# fab.net
KiCad netlist of a schematic drawn in Altium Designer
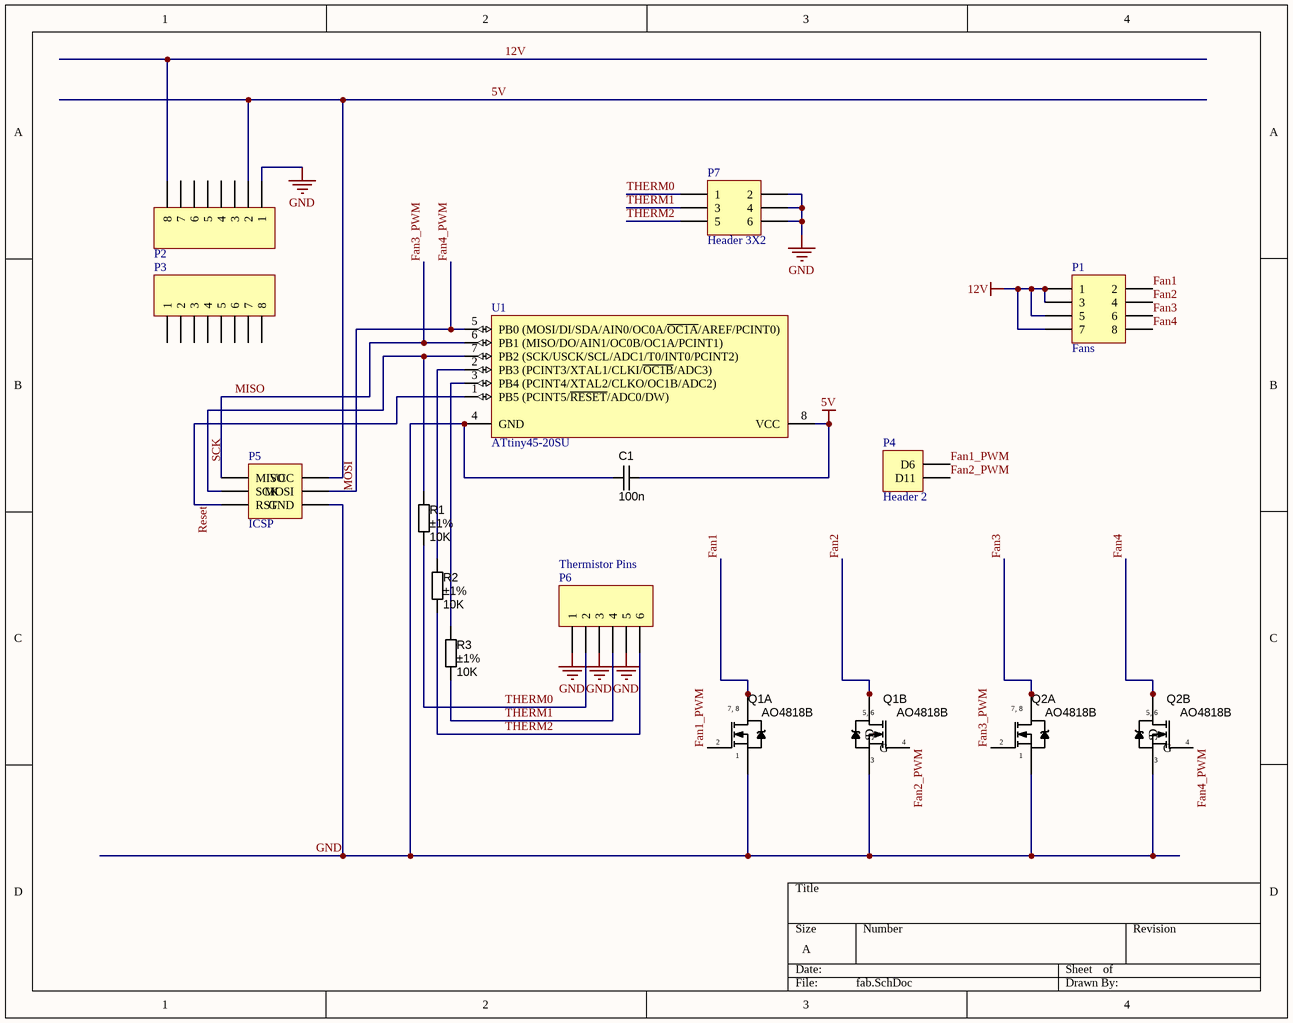
[diagram p0: fab.SchDoc]

(export (version "E")
  (design (tool "Eeschema 10.0.6"))
  (components
    (comp (ref "C1")
      (value "100n")
      (footprint "CAPC1005X55N")
      (description "Capacitor SMD Cer 100nF 10% 16V X5R 0402")
      (fields (field (name "TOLERANCE") "±10%"))
      (libsource (lib "PBL - Capacitors") (part "CAPC_100n_0402_X5R_16V_10%"))
    )
    (comp (ref "P1")
      (value "Fans")
      (footprint "HDR2X4")
      (description "Header, 4-Pin, Dual row")
      (fields (field (name "PUBLISHER") "Altium Limited"))
      (libsource (lib "Miscellaneous Connectors") (part "Header 4X2"))
    )
    (comp (ref "P2")
      (value "Header 8")
      (footprint "HDR1X8")
      (description "Header, 8-Pin")
      (fields (field (name "PUBLISHER") "Altium Limited"))
      (libsource (lib "Miscellaneous Connectors") (part "Header 8"))
    )
    (comp (ref "P3")
      (value "Header 8")
      (footprint "HDR1X8")
      (description "Header, 8-Pin")
      (fields (field (name "PUBLISHER") "Altium Limited"))
      (libsource (lib "") (part "Header 8_1"))
    )
    (comp (ref "P4")
      (value "Header 2")
      (footprint "HDR1X2")
      (description "Header, 2-Pin")
      (fields (field (name "PUBLISHER") "Altium Limited"))
      (libsource (lib "Miscellaneous Connectors") (part "Header 2"))
    )
    (comp (ref "P5")
      (value "ICSP")
      (footprint "ICSP Pads - SMD")
      (description "Header, 3-Pin, Dual row")
      (fields (field (name "PUBLISHER") "Altium Limited"))
      (libsource (lib "") (part "Header 3X2_1"))
    )
    (comp (ref "P6")
      (value "Thermistor Pins")
      (footprint "HDR1X6")
      (description "Header, 6-Pin")
      (fields (field (name "PUBLISHER") "Altium Limited"))
      (libsource (lib "Miscellaneous Connectors") (part "Header 6"))
    )
    (comp (ref "P7")
      (value "Header 3X2")
      (footprint "HDR2X3")
      (description "Header, 3-Pin, Dual row")
      (fields (field (name "PUBLISHER") "Altium Limited"))
      (libsource (lib "Miscellaneous Connectors") (part "Header 3X2"))
    )
    (comp (ref "Q1")
      (value "MOSFET_AO4818B")
      (footprint "SOIC127P600X175-8AN")
      (description "MOSFET Dual-Channel 30V 8.5A SOIC-8 SMD")
      (fields (field (name "MANUFACTURER PART NUMBER 1") "AO4818B"))
      (libsource (lib "PBL - Transistors") (part "MOSFET_AO4818B"))
    )
    (comp (ref "Q2")
      (value "MOSFET_AO4818B")
      (footprint "SOIC127P600X175-8AN")
      (description "MOSFET Dual-Channel 30V 8.5A SOIC-8 SMD")
      (fields (field (name "MANUFACTURER PART NUMBER 1") "AO4818B"))
      (libsource (lib "") (part "MOSFET_AO4818B_1"))
    )
    (comp (ref "R1")
      (value "10K")
      (footprint "RESC1608X55N")
      (description "Resistor SMD chip 10k Ohm 0.1W 1% 0603")
      (fields (field (name "TOLERANCE") "±1%") (field (name "Comment") "Thick Film"))
      (libsource (lib "PBL - Resistors") (part "RES_10K_0603_1%"))
    )
    (comp (ref "R2")
      (value "10K")
      (footprint "RESC1608X55N")
      (description "Resistor SMD chip 10k Ohm 0.1W 1% 0603")
      (fields (field (name "TOLERANCE") "±1%") (field (name "Comment") "Thick Film"))
      (libsource (lib "PBL - Resistors") (part "RES_10K_0603_1%"))
    )
    (comp (ref "R3")
      (value "10K")
      (footprint "RESC1608X55N")
      (description "Resistor SMD chip 10k Ohm 0.1W 1% 0603")
      (fields (field (name "TOLERANCE") "±1%") (field (name "Comment") "Thick Film"))
      (libsource (lib "PBL - Resistors") (part "RES_10K_0603_1%"))
    )
    (comp (ref "U1")
      (value "ATtiny45-20SU")
      (footprint "8S2_N")
      (libsource (lib "Atmel Microcontroller tinyAVR") (part "ATtiny45-20SU"))
    )
  )
  (nets
    (net (code "1") (name "/Fan1") (class "Default")
      (node (ref "P1") (pin "2") (pinfunction "2_2") (pintype "passive"))
      (node (ref "Q1") (pin "7") (pinfunction "D_7") (pintype "passive"))
      (node (ref "Q1") (pin "8") (pinfunction "D_8") (pintype "passive"))
    )
    (net (code "2") (name "/Fan1_PWM") (class "Default")
      (node (ref "P4") (pin "2") (pinfunction "D6_2") (pintype "passive"))
      (node (ref "Q1") (pin "2") (pinfunction "G_2") (pintype "passive"))
    )
    (net (code "3") (name "/Fan2") (class "Default")
      (node (ref "P1") (pin "4") (pinfunction "4_4") (pintype "passive"))
      (node (ref "Q1") (pin "5") (pinfunction "D_5") (pintype "passive"))
      (node (ref "Q1") (pin "6") (pinfunction "D_6") (pintype "passive"))
    )
    (net (code "4") (name "/Fan2_PWM") (class "Default")
      (node (ref "P4") (pin "1") (pinfunction "D11_1") (pintype "passive"))
      (node (ref "Q1") (pin "4") (pinfunction "G_4") (pintype "passive"))
    )
    (net (code "5") (name "/Fan3") (class "Default")
      (node (ref "P1") (pin "6") (pinfunction "6_6") (pintype "passive"))
      (node (ref "Q2") (pin "7") (pinfunction "D_7") (pintype "passive"))
      (node (ref "Q2") (pin "8") (pinfunction "D_8") (pintype "passive"))
    )
    (net (code "6") (name "/Fan3_PWM") (class "Default")
      (node (ref "P5") (pin "0") (pinfunction "MISO_0") (pintype "passive"))
      (node (ref "Q2") (pin "2") (pinfunction "G_2") (pintype "passive"))
      (node (ref "U1") (pin "6") (pinfunction "PB1_(MISO/DO/AIN1/OC0B/OC1A/PCINT1)_6") (pintype "bidirectional"))
    )
    (net (code "7") (name "/Fan4") (class "Default")
      (node (ref "P1") (pin "8") (pinfunction "8_8") (pintype "passive"))
      (node (ref "Q2") (pin "5") (pinfunction "D_5") (pintype "passive"))
      (node (ref "Q2") (pin "6") (pinfunction "D_6") (pintype "passive"))
    )
    (net (code "8") (name "/Fan4_PWM") (class "Default")
      (node (ref "P5") (pin "3") (pinfunction "MOSI_3") (pintype "passive"))
      (node (ref "Q2") (pin "4") (pinfunction "G_4") (pintype "passive"))
      (node (ref "U1") (pin "5") (pinfunction "PB0_(MOSI/DI/SDA/AIN0/OC0A/~{OC1A}/AREF/PCINT0)_5") (pintype "bidirectional"))
    )
    (net (code "9") (name "/Reset") (class "Default")
      (node (ref "P5") (pin "4") (pinfunction "RST_4") (pintype "passive"))
      (node (ref "U1") (pin "1") (pinfunction "PB5_(PCINT5/~{RESET}/ADC0/DW)_1") (pintype "bidirectional"))
    )
    (net (code "10") (name "/SCK") (class "Default")
      (node (ref "P5") (pin "2") (pinfunction "SCK_2") (pintype "passive"))
      (node (ref "R1") (pin "1") (pinfunction "1_1") (pintype "passive"))
      (node (ref "U1") (pin "7") (pinfunction "PB2_(SCK/USCK/SCL/ADC1/T0/INT0/PCINT2)_7") (pintype "bidirectional"))
    )
    (net (code "11") (name "/THERM0") (class "Default")
      (node (ref "P6") (pin "2") (pinfunction "2_2") (pintype "passive"))
      (node (ref "P7") (pin "1") (pinfunction "1_1") (pintype "passive"))
      (node (ref "R1") (pin "2") (pinfunction "2_2") (pintype "passive"))
    )
    (net (code "12") (name "/THERM1") (class "Default")
      (node (ref "P6") (pin "4") (pinfunction "4_4") (pintype "passive"))
      (node (ref "P7") (pin "3") (pinfunction "3_3") (pintype "passive"))
      (node (ref "R3") (pin "2") (pinfunction "2_2") (pintype "passive"))
    )
    (net (code "13") (name "/THERM2") (class "Default")
      (node (ref "P6") (pin "6") (pinfunction "6_6") (pintype "passive"))
      (node (ref "P7") (pin "5") (pinfunction "5_5") (pintype "passive"))
      (node (ref "R2") (pin "2") (pinfunction "2_2") (pintype "passive"))
    )
    (net (code "14") (name "5V") (class "Default")
      (node (ref "C1") (pin "2") (pintype "passive"))
      (node (ref "P2") (pin "2") (pinfunction "2_2") (pintype "passive"))
      (node (ref "P5") (pin "1") (pinfunction "VCC_1") (pintype "passive"))
      (node (ref "U1") (pin "8") (pinfunction "VCC_8") (pintype "power_in"))
    )
    (net (code "15") (name "12V") (class "Default")
      (node (ref "P1") (pin "1") (pinfunction "1_1") (pintype "passive"))
      (node (ref "P1") (pin "3") (pinfunction "3_3") (pintype "passive"))
      (node (ref "P1") (pin "5") (pinfunction "5_5") (pintype "passive"))
      (node (ref "P1") (pin "7") (pinfunction "7_7") (pintype "passive"))
      (node (ref "P2") (pin "8") (pinfunction "8_8") (pintype "passive"))
    )
    (net (code "16") (name "GND") (class "Default")
      (node (ref "C1") (pin "1") (pintype "passive"))
      (node (ref "P2") (pin "1") (pinfunction "1_1") (pintype "passive"))
      (node (ref "P5") (pin "5") (pinfunction "GND_5") (pintype "passive"))
      (node (ref "P6") (pin "1") (pinfunction "1_1") (pintype "passive"))
      (node (ref "P6") (pin "3") (pinfunction "3_3") (pintype "passive"))
      (node (ref "P6") (pin "5") (pinfunction "5_5") (pintype "passive"))
      (node (ref "P7") (pin "2") (pinfunction "2_2") (pintype "passive"))
      (node (ref "P7") (pin "4") (pinfunction "4_4") (pintype "passive"))
      (node (ref "P7") (pin "6") (pinfunction "6_6") (pintype "passive"))
      (node (ref "Q1") (pin "1") (pinfunction "S_1") (pintype "passive"))
      (node (ref "Q1") (pin "3") (pinfunction "S_3") (pintype "passive"))
      (node (ref "Q2") (pin "1") (pinfunction "S_1") (pintype "passive"))
      (node (ref "Q2") (pin "3") (pinfunction "S_3") (pintype "passive"))
      (node (ref "U1") (pin "4") (pinfunction "GND_4") (pintype "power_in"))
    )
    (net (code "17") (name "Net-(U1-PB3_(PCINT3{slash}XTAL1{slash}CLKI{slash}~{OC1B}{slash}ADC3))") (class "Default")
      (node (ref "R2") (pin "1") (pinfunction "1_1") (pintype "passive"))
      (node (ref "U1") (pin "2") (pinfunction "PB3_(PCINT3/XTAL1/CLKI/~{OC1B}/ADC3)_2") (pintype "bidirectional"))
    )
    (net (code "18") (name "Net-(U1-PB4_(PCINT4{slash}XTAL2{slash}CLKO{slash}OC1B{slash}ADC2))") (class "Default")
      (node (ref "R3") (pin "1") (pinfunction "1_1") (pintype "passive"))
      (node (ref "U1") (pin "3") (pinfunction "PB4_(PCINT4/XTAL2/CLKO/OC1B/ADC2)_3") (pintype "bidirectional"))
    )
    (net (code "19") (name "unconnected-(P2-Pad3)") (class "Default")
      (node (ref "P2") (pin "3") (pinfunction "3_3") (pintype "passive"))
    )
    (net (code "20") (name "unconnected-(P2-Pad4)") (class "Default")
      (node (ref "P2") (pin "4") (pinfunction "4_4") (pintype "passive"))
    )
    (net (code "21") (name "unconnected-(P2-Pad5)") (class "Default")
      (node (ref "P2") (pin "5") (pinfunction "5_5") (pintype "passive"))
    )
    (net (code "22") (name "unconnected-(P2-Pad6)") (class "Default")
      (node (ref "P2") (pin "6") (pinfunction "6_6") (pintype "passive"))
    )
    (net (code "23") (name "unconnected-(P2-Pad7)") (class "Default")
      (node (ref "P2") (pin "7") (pinfunction "7_7") (pintype "passive"))
    )
    (net (code "24") (name "unconnected-(P3-Pad1)") (class "Default")
      (node (ref "P3") (pin "1") (pinfunction "1_1") (pintype "passive"))
    )
    (net (code "25") (name "unconnected-(P3-Pad2)") (class "Default")
      (node (ref "P3") (pin "2") (pinfunction "2_2") (pintype "passive"))
    )
    (net (code "26") (name "unconnected-(P3-Pad3)") (class "Default")
      (node (ref "P3") (pin "3") (pinfunction "3_3") (pintype "passive"))
    )
    (net (code "27") (name "unconnected-(P3-Pad4)") (class "Default")
      (node (ref "P3") (pin "4") (pinfunction "4_4") (pintype "passive"))
    )
    (net (code "28") (name "unconnected-(P3-Pad5)") (class "Default")
      (node (ref "P3") (pin "5") (pinfunction "5_5") (pintype "passive"))
    )
    (net (code "29") (name "unconnected-(P3-Pad6)") (class "Default")
      (node (ref "P3") (pin "6") (pinfunction "6_6") (pintype "passive"))
    )
    (net (code "30") (name "unconnected-(P3-Pad7)") (class "Default")
      (node (ref "P3") (pin "7") (pinfunction "7_7") (pintype "passive"))
    )
    (net (code "31") (name "unconnected-(P3-Pad8)") (class "Default")
      (node (ref "P3") (pin "8") (pinfunction "8_8") (pintype "passive"))
    )
  )
)
